# SunS_fixture_EGSE_UART_Isolation.net
KiCad netlist of a schematic drawn in Altium Designer
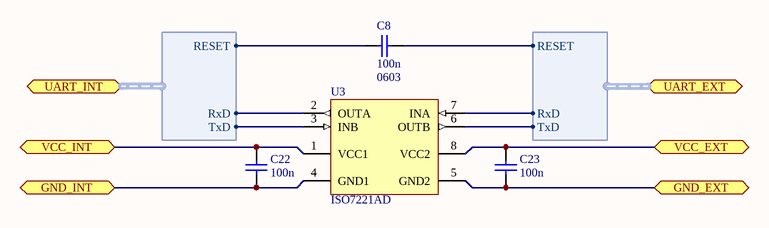
[diagram p0: SunS_fixture_EGSE_UART_Isolation.SchDoc]

(export (version "E")
  (design (tool "Eeschema 10.0.6"))
  (components
    (comp (ref "C8")
      (value "100n")
      (footprint "SMD_Capacitor_0603")
      (description "Cap")
      (fields (field (name "PACKAGE") "0603"))
      (libsource (lib "capacitors") (part "Cap"))
    )
    (comp (ref "C22")
      (value "100n")
      (footprint "SMD_Capacitor_0603")
      (description "Cap")
      (libsource (lib "capacitors") (part "Cap"))
    )
    (comp (ref "C23")
      (value "100n")
      (footprint "SMD_Capacitor_0603")
      (description "Cap")
      (libsource (lib "capacitors") (part "Cap"))
    )
    (comp (ref "U3")
      (value "ISO7221AD")
      (footprint "D0008A_N")
      (fields (field (name "MANUFACTURER") "Texas Instruments"))
      (libsource (lib "TI Interface Isolator") (part "ISO7221AD"))
    )
  )
  (nets
    (net (code "2") (name "/GND_EXT") (class "Default")
      (node (ref "C23") (pin "2") (pinfunction "2_2") (pintype "passive"))
      (node (ref "U3") (pin "5") (pinfunction "GND2_5") (pintype "power_in"))
    )
    (net (code "3") (name "/GND_INT") (class "Default")
      (node (ref "C22") (pin "2") (pinfunction "2_2") (pintype "passive"))
      (node (ref "U3") (pin "4") (pinfunction "GND1_4") (pintype "power_in"))
    )
    (net (code "4") (name "/VCC_EXT") (class "Default")
      (node (ref "C23") (pin "1") (pinfunction "1_1") (pintype "passive"))
      (node (ref "U3") (pin "8") (pinfunction "VCC2_8") (pintype "power_in"))
    )
    (net (code "5") (name "/VCC_INT") (class "Default")
      (node (ref "C22") (pin "1") (pinfunction "1_1") (pintype "passive"))
      (node (ref "U3") (pin "1") (pinfunction "VCC1_1") (pintype "power_in"))
    )
    (net (code "7") (name "unconnected-(C8-Pad1)") (class "Default")
      (node (ref "C8") (pin "1") (pinfunction "1_1") (pintype "passive"))
    )
    (net (code "8") (name "unconnected-(C8-Pad2)") (class "Default")
      (node (ref "C8") (pin "2") (pinfunction "2_2") (pintype "passive"))
    )
    (net (code "9") (name "unconnected-(U3-INA-Pad7)") (class "Default")
      (node (ref "U3") (pin "7") (pinfunction "INA_7") (pintype "input"))
    )
    (net (code "10") (name "unconnected-(U3-INB-Pad3)") (class "Default")
      (node (ref "U3") (pin "3") (pinfunction "INB_3") (pintype "input"))
    )
    (net (code "11") (name "unconnected-(U3-OUTA-Pad2)") (class "Default")
      (node (ref "U3") (pin "2") (pinfunction "OUTA_2") (pintype "output"))
    )
    (net (code "12") (name "unconnected-(U3-OUTB-Pad6)") (class "Default")
      (node (ref "U3") (pin "6") (pinfunction "OUTB_6") (pintype "output"))
    )
  )
)
